# Motor_Control_Thermal_Vias.net
KiCad netlist of a schematic drawn in EAGLE
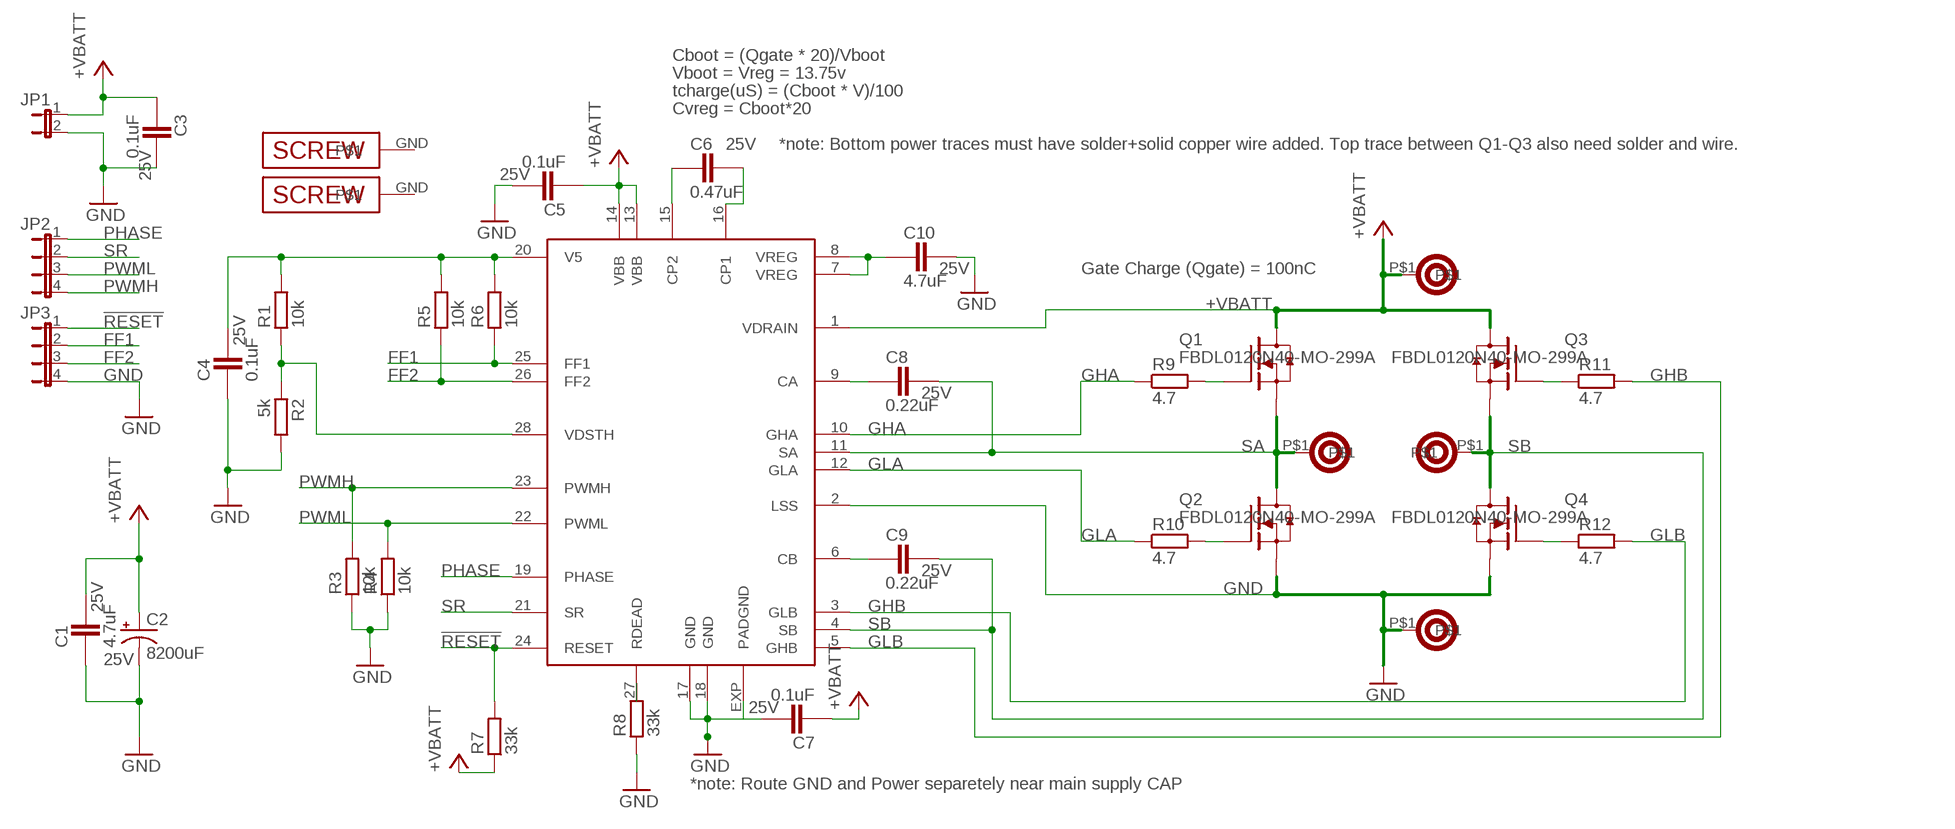
[diagram p0: schematic, sheet 1]

(export (version "E")
  (design (tool "Eeschema 10.0.6"))
  (components
    (comp (ref "C1")
      (value "4.7uF")
      (footprint "eagle-import:CAPC1608X92N")
      (fields (field (name "VOLTAGE") "25V"))
      (libsource (lib "eagle-import") (part "CAPACITOR_0603"))
    )
    (comp (ref "C2")
      (value "8200uF")
      (footprint "eagle-import:CAP-10-22")
      (fields
        (field (name "MANUFACTURER") "Panasonic")
        (field (name "MANUFACTURER_PART_NUMBER") "ECO-S1EA822BA")
        (field (name "VOLTAGE") "25V")
      )
      (libsource (lib "eagle-import") (part "CPOL-US-PTH-10-22"))
    )
    (comp (ref "C3")
      (value "0.1uF")
      (footprint "eagle-import:CAPC1608X92N")
      (fields (field (name "VOLTAGE") "25V"))
      (libsource (lib "eagle-import") (part "CAPACITOR_0603"))
    )
    (comp (ref "C4")
      (value "0.1uF")
      (footprint "eagle-import:CAPC_0603_LONG")
      (fields (field (name "VOLTAGE") "25V"))
      (libsource (lib "eagle-import") (part "CAPACITOR_0603L"))
    )
    (comp (ref "C5")
      (value "0.1uF")
      (footprint "eagle-import:CAPC1608X92N")
      (fields (field (name "VOLTAGE") "25V"))
      (libsource (lib "eagle-import") (part "CAPACITOR_0603"))
    )
    (comp (ref "C6")
      (value "0.47uF")
      (footprint "eagle-import:CAPC1608X92N")
      (fields (field (name "VOLTAGE") "25V"))
      (libsource (lib "eagle-import") (part "CAPACITOR_0603"))
    )
    (comp (ref "C7")
      (value "0.1uF")
      (footprint "eagle-import:CAPC1608X92N")
      (fields (field (name "VOLTAGE") "25V"))
      (libsource (lib "eagle-import") (part "CAPACITOR_0603"))
    )
    (comp (ref "C8")
      (value "0.22uF")
      (footprint "eagle-import:CAPC_0603_LONG")
      (fields (field (name "VOLTAGE") "25V"))
      (libsource (lib "eagle-import") (part "CAPACITOR_0603L"))
    )
    (comp (ref "C9")
      (value "0.22uF")
      (footprint "eagle-import:CAPC_0603_LONG")
      (fields (field (name "VOLTAGE") "25V"))
      (libsource (lib "eagle-import") (part "CAPACITOR_0603L"))
    )
    (comp (ref "C10")
      (value "4.7uF")
      (footprint "eagle-import:CAPC1608X92N")
      (fields (field (name "VOLTAGE") "25V"))
      (libsource (lib "eagle-import") (part "CAPACITOR_0603"))
    )
    (comp (ref "J1")
      (value "63971-1-QC_TAB-RA")
      (footprint "eagle-import:QUICK_CONN_TAB-RA")
      (fields
        (field (name "MANUFACTURER") "TE Connectivity")
        (field (name "MANUFACTURER_PART_NUMBER") "63971-1")
      )
      (libsource (lib "eagle-import") (part "63971-1-QC_TAB-RA"))
    )
    (comp (ref "J2")
      (value "63971-1-QC_TAB-RA")
      (footprint "eagle-import:QUICK_CONN_TAB-RA")
      (fields
        (field (name "MANUFACTURER") "TE Connectivity")
        (field (name "MANUFACTURER_PART_NUMBER") "63971-1")
      )
      (libsource (lib "eagle-import") (part "63971-1-QC_TAB-RA"))
    )
    (comp (ref "J3")
      (value "63971-1-QC_TAB-RA")
      (footprint "eagle-import:QUICK_CONN_TAB-RA")
      (fields
        (field (name "MANUFACTURER") "TE Connectivity")
        (field (name "MANUFACTURER_PART_NUMBER") "63971-1")
      )
      (libsource (lib "eagle-import") (part "63971-1-QC_TAB-RA"))
    )
    (comp (ref "J4")
      (value "63971-1-QC_TAB-RA")
      (footprint "eagle-import:QUICK_CONN_TAB-RA")
      (fields
        (field (name "MANUFACTURER") "TE Connectivity")
        (field (name "MANUFACTURER_PART_NUMBER") "63971-1")
      )
      (libsource (lib "eagle-import") (part "63971-1-QC_TAB-RA"))
    )
    (comp (ref "JP1")
      (value "JP1E")
      (footprint "eagle-import:JP1")
      (libsource (lib "eagle-import") (part "JP1E"))
    )
    (comp (ref "JP2")
      (value "JP4E")
      (footprint "eagle-import:JP4")
      (libsource (lib "eagle-import") (part "JP4E"))
    )
    (comp (ref "JP3")
      (value "JP4E")
      (footprint "eagle-import:JP4")
      (libsource (lib "eagle-import") (part "JP4E"))
    )
    (comp (ref "Q1")
      (value "FBDL0120N40-MO-299A")
      (footprint "eagle-import:MO-299")
      (fields
        (field (name "MANUFACTURER") "Fairchild")
        (field (name "MANUFACTURER_PART_NUMBER") "FDBL0120N40")
      )
      (libsource (lib "eagle-import") (part "FBDL0120N40-MO-299A"))
    )
    (comp (ref "Q2")
      (value "FBDL0120N40-MO-299A")
      (footprint "eagle-import:MO-299")
      (fields
        (field (name "MANUFACTURER") "Fairchild")
        (field (name "MANUFACTURER_PART_NUMBER") "FDBL0120N40")
      )
      (libsource (lib "eagle-import") (part "FBDL0120N40-MO-299A"))
    )
    (comp (ref "Q3")
      (value "FBDL0120N40-MO-299A")
      (footprint "eagle-import:MO-299")
      (fields
        (field (name "MANUFACTURER") "Fairchild")
        (field (name "MANUFACTURER_PART_NUMBER") "FDBL0120N40")
      )
      (libsource (lib "eagle-import") (part "FBDL0120N40-MO-299A"))
    )
    (comp (ref "Q4")
      (value "FBDL0120N40-MO-299A")
      (footprint "eagle-import:MO-299")
      (fields
        (field (name "MANUFACTURER") "Fairchild")
        (field (name "MANUFACTURER_PART_NUMBER") "FDBL0120N40")
      )
      (libsource (lib "eagle-import") (part "FBDL0120N40-MO-299A"))
    )
    (comp (ref "R1")
      (value "10k")
      (footprint "eagle-import:RESC1608X55N")
      (libsource (lib "eagle-import") (part "RESISTOR_0603"))
    )
    (comp (ref "R2")
      (value "5k")
      (footprint "eagle-import:RESC1608X55N")
      (libsource (lib "eagle-import") (part "RESISTOR_0603"))
    )
    (comp (ref "R3")
      (value "10k")
      (footprint "eagle-import:RESC1608X55N")
      (libsource (lib "eagle-import") (part "RESISTOR_0603"))
    )
    (comp (ref "R4")
      (value "10k")
      (footprint "eagle-import:RESC1608X55N")
      (libsource (lib "eagle-import") (part "RESISTOR_0603"))
    )
    (comp (ref "R5")
      (value "10k")
      (footprint "eagle-import:RESC1608X55N")
      (libsource (lib "eagle-import") (part "RESISTOR_0603"))
    )
    (comp (ref "R6")
      (value "10k")
      (footprint "eagle-import:RESC1608X55N")
      (libsource (lib "eagle-import") (part "RESISTOR_0603"))
    )
    (comp (ref "R7")
      (value "33k")
      (footprint "eagle-import:RESC1608X55N")
      (libsource (lib "eagle-import") (part "RESISTOR_0603"))
    )
    (comp (ref "R8")
      (value "33k")
      (footprint "eagle-import:RESC1608X55N")
      (libsource (lib "eagle-import") (part "RESISTOR_0603"))
    )
    (comp (ref "R9")
      (value "4.7")
      (footprint "eagle-import:RESC1608X55N")
      (libsource (lib "eagle-import") (part "RESISTOR_0603"))
    )
    (comp (ref "R10")
      (value "4.7")
      (footprint "eagle-import:RESC1608X55N")
      (libsource (lib "eagle-import") (part "RESISTOR_0603"))
    )
    (comp (ref "R11")
      (value "4.7")
      (footprint "eagle-import:RESC1608X55N")
      (libsource (lib "eagle-import") (part "RESISTOR_0603"))
    )
    (comp (ref "R12")
      (value "4.7")
      (footprint "eagle-import:RESC1608X55N")
      (libsource (lib "eagle-import") (part "RESISTOR_0603"))
    )
    (comp (ref "SCREW1")
      (value "SCREW-4MM")
      (footprint "eagle-import:PLATEDSCREW-4MM")
      (libsource (lib "eagle-import") (part "SCREW-4MM"))
    )
    (comp (ref "SCREW2")
      (value "SCREW-4MM")
      (footprint "eagle-import:PLATEDSCREW-4MM")
      (libsource (lib "eagle-import") (part "SCREW-4MM"))
    )
    (comp (ref "U1")
      (value "A3941-TSSOP28-LP")
      (footprint "eagle-import:TSSOP28-LP")
      (fields
        (field (name "MANUFACTURER") "Allegro MicroSystems LLC")
        (field (name "MANUFACTURER_PART_NUMBER") "A3941")
      )
      (libsource (lib "eagle-import") (part "A3941-TSSOP28-LP"))
    )
  )
  (nets
    (net (code "1") (name "+VBATT") (class "Default")
      (node (ref "C1") (pin "2") (pinfunction "2_2") (pintype "passive"))
      (node (ref "C2") (pin "+") (pinfunction "+_+") (pintype "passive"))
      (node (ref "C3") (pin "1") (pinfunction "1_1") (pintype "passive"))
      (node (ref "C5") (pin "1") (pinfunction "1_1") (pintype "passive"))
      (node (ref "C7") (pin "1") (pinfunction "1_1") (pintype "passive"))
      (node (ref "J2") (pin "P$1") (pinfunction "P$1_P$1") (pintype "bidirectional"))
      (node (ref "JP1") (pin "1") (pinfunction "1_1") (pintype "passive"))
      (node (ref "Q1") (pin "P$9") (pinfunction "D_P$9") (pintype "passive"))
      (node (ref "Q3") (pin "P$9") (pinfunction "D_P$9") (pintype "passive"))
      (node (ref "R7") (pin "1") (pinfunction "1_1") (pintype "passive"))
      (node (ref "U1") (pin "1") (pinfunction "VDRAIN_1") (pintype "bidirectional"))
      (node (ref "U1") (pin "13") (pinfunction "VBB_13") (pintype "bidirectional"))
      (node (ref "U1") (pin "14") (pinfunction "VBB_14") (pintype "bidirectional"))
    )
    (net (code "2") (name "/FF1") (class "Default")
      (node (ref "JP3") (pin "2") (pinfunction "2_2") (pintype "passive"))
      (node (ref "R6") (pin "1") (pinfunction "1_1") (pintype "passive"))
      (node (ref "U1") (pin "25") (pinfunction "FF1_25") (pintype "output"))
    )
    (net (code "3") (name "/FF2") (class "Default")
      (node (ref "JP3") (pin "3") (pinfunction "3_3") (pintype "passive"))
      (node (ref "R5") (pin "1") (pinfunction "1_1") (pintype "passive"))
      (node (ref "U1") (pin "26") (pinfunction "FF2_26") (pintype "output"))
    )
    (net (code "4") (name "/GHA") (class "Default")
      (node (ref "R9") (pin "1") (pinfunction "1_1") (pintype "passive"))
      (node (ref "U1") (pin "10") (pinfunction "GHA_10") (pintype "output"))
    )
    (net (code "5") (name "/GHB") (class "Default")
      (node (ref "R11") (pin "2") (pinfunction "2_2") (pintype "passive"))
      (node (ref "U1") (pin "5") (pinfunction "GHB_5") (pintype "output"))
    )
    (net (code "6") (name "/GLA") (class "Default")
      (node (ref "R10") (pin "1") (pinfunction "1_1") (pintype "passive"))
      (node (ref "U1") (pin "12") (pinfunction "GLA_12") (pintype "output"))
    )
    (net (code "7") (name "/GLB") (class "Default")
      (node (ref "R12") (pin "2") (pinfunction "2_2") (pintype "passive"))
      (node (ref "U1") (pin "3") (pinfunction "GLB_3") (pintype "output"))
    )
    (net (code "8") (name "/PHASE") (class "Default")
      (node (ref "JP2") (pin "1") (pinfunction "1_1") (pintype "passive"))
      (node (ref "U1") (pin "19") (pinfunction "PHASE_19") (pintype "input"))
    )
    (net (code "9") (name "/PWMH") (class "Default")
      (node (ref "JP2") (pin "4") (pinfunction "4_4") (pintype "passive"))
      (node (ref "R3") (pin "2") (pinfunction "2_2") (pintype "passive"))
      (node (ref "U1") (pin "23") (pinfunction "PWMH_23") (pintype "input"))
    )
    (net (code "10") (name "/PWML") (class "Default")
      (node (ref "JP2") (pin "3") (pinfunction "3_3") (pintype "passive"))
      (node (ref "R4") (pin "2") (pinfunction "2_2") (pintype "passive"))
      (node (ref "U1") (pin "22") (pinfunction "PWML_22") (pintype "input"))
    )
    (net (code "11") (name "/SA") (class "Default")
      (node (ref "C8") (pin "2") (pinfunction "2_2") (pintype "passive"))
      (node (ref "J1") (pin "P$1") (pinfunction "P$1_P$1") (pintype "bidirectional"))
      (node (ref "Q1") (pin "P$2") (pinfunction "S_P$2") (pintype "passive"))
      (node (ref "Q1") (pin "P$3") (pinfunction "S_P$3") (pintype "passive"))
      (node (ref "Q1") (pin "P$4") (pinfunction "S_P$4") (pintype "passive"))
      (node (ref "Q1") (pin "P$5") (pinfunction "S_P$5") (pintype "passive"))
      (node (ref "Q1") (pin "P$6") (pinfunction "S_P$6") (pintype "passive"))
      (node (ref "Q1") (pin "P$7") (pinfunction "S_P$7") (pintype "passive"))
      (node (ref "Q1") (pin "P$8") (pinfunction "S_P$8") (pintype "passive"))
      (node (ref "Q2") (pin "P$9") (pinfunction "D_P$9") (pintype "passive"))
      (node (ref "U1") (pin "11") (pinfunction "SA_11") (pintype "bidirectional"))
    )
    (net (code "12") (name "/SB") (class "Default")
      (node (ref "C9") (pin "2") (pinfunction "2_2") (pintype "passive"))
      (node (ref "J3") (pin "P$1") (pinfunction "P$1_P$1") (pintype "bidirectional"))
      (node (ref "Q3") (pin "P$2") (pinfunction "S_P$2") (pintype "passive"))
      (node (ref "Q3") (pin "P$3") (pinfunction "S_P$3") (pintype "passive"))
      (node (ref "Q3") (pin "P$4") (pinfunction "S_P$4") (pintype "passive"))
      (node (ref "Q3") (pin "P$5") (pinfunction "S_P$5") (pintype "passive"))
      (node (ref "Q3") (pin "P$6") (pinfunction "S_P$6") (pintype "passive"))
      (node (ref "Q3") (pin "P$7") (pinfunction "S_P$7") (pintype "passive"))
      (node (ref "Q3") (pin "P$8") (pinfunction "S_P$8") (pintype "passive"))
      (node (ref "Q4") (pin "P$9") (pinfunction "D_P$9") (pintype "passive"))
      (node (ref "U1") (pin "4") (pinfunction "SB_4") (pintype "bidirectional"))
    )
    (net (code "13") (name "/SR") (class "Default")
      (node (ref "JP2") (pin "2") (pinfunction "2_2") (pintype "passive"))
      (node (ref "U1") (pin "21") (pinfunction "SR_21") (pintype "input"))
    )
    (net (code "14") (name "/~{RESET}") (class "Default")
      (node (ref "JP3") (pin "1") (pinfunction "1_1") (pintype "passive"))
      (node (ref "R7") (pin "2") (pinfunction "2_2") (pintype "passive"))
      (node (ref "U1") (pin "24") (pinfunction "RESET_24") (pintype "input"))
    )
    (net (code "15") (name "GND") (class "Default")
      (node (ref "C1") (pin "1") (pinfunction "1_1") (pintype "passive"))
      (node (ref "C10") (pin "2") (pinfunction "2_2") (pintype "passive"))
      (node (ref "C2") (pin "-") (pinfunction "-_-") (pintype "passive"))
      (node (ref "C3") (pin "2") (pinfunction "2_2") (pintype "passive"))
      (node (ref "C4") (pin "1") (pinfunction "1_1") (pintype "passive"))
      (node (ref "C5") (pin "2") (pinfunction "2_2") (pintype "passive"))
      (node (ref "C7") (pin "2") (pinfunction "2_2") (pintype "passive"))
      (node (ref "J4") (pin "P$1") (pinfunction "P$1_P$1") (pintype "bidirectional"))
      (node (ref "JP1") (pin "2") (pinfunction "2_2") (pintype "passive"))
      (node (ref "JP3") (pin "4") (pinfunction "4_4") (pintype "passive"))
      (node (ref "Q2") (pin "P$2") (pinfunction "S_P$2") (pintype "passive"))
      (node (ref "Q2") (pin "P$3") (pinfunction "S_P$3") (pintype "passive"))
      (node (ref "Q2") (pin "P$4") (pinfunction "S_P$4") (pintype "passive"))
      (node (ref "Q2") (pin "P$5") (pinfunction "S_P$5") (pintype "passive"))
      (node (ref "Q2") (pin "P$6") (pinfunction "S_P$6") (pintype "passive"))
      (node (ref "Q2") (pin "P$7") (pinfunction "S_P$7") (pintype "passive"))
      (node (ref "Q2") (pin "P$8") (pinfunction "S_P$8") (pintype "passive"))
      (node (ref "Q4") (pin "P$2") (pinfunction "S_P$2") (pintype "passive"))
      (node (ref "Q4") (pin "P$3") (pinfunction "S_P$3") (pintype "passive"))
      (node (ref "Q4") (pin "P$4") (pinfunction "S_P$4") (pintype "passive"))
      (node (ref "Q4") (pin "P$5") (pinfunction "S_P$5") (pintype "passive"))
      (node (ref "Q4") (pin "P$6") (pinfunction "S_P$6") (pintype "passive"))
      (node (ref "Q4") (pin "P$7") (pinfunction "S_P$7") (pintype "passive"))
      (node (ref "Q4") (pin "P$8") (pinfunction "S_P$8") (pintype "passive"))
      (node (ref "R2") (pin "2") (pinfunction "2_2") (pintype "passive"))
      (node (ref "R3") (pin "1") (pinfunction "1_1") (pintype "passive"))
      (node (ref "R4") (pin "1") (pinfunction "1_1") (pintype "passive"))
      (node (ref "R8") (pin "1") (pinfunction "1_1") (pintype "passive"))
      (node (ref "U1") (pin "17") (pinfunction "GND_17") (pintype "bidirectional"))
      (node (ref "U1") (pin "18") (pinfunction "GND_18") (pintype "bidirectional"))
      (node (ref "U1") (pin "2") (pinfunction "LSS_2") (pintype "bidirectional"))
      (node (ref "U1") (pin "EXP") (pinfunction "PADGND_EXP") (pintype "bidirectional"))
    )
    (net (code "16") (name "Net-(C10-Pad1)") (class "Default")
      (node (ref "C10") (pin "1") (pinfunction "1_1") (pintype "passive"))
      (node (ref "U1") (pin "7") (pinfunction "VREG_7") (pintype "bidirectional"))
      (node (ref "U1") (pin "8") (pinfunction "VREG_8") (pintype "bidirectional"))
    )
    (net (code "17") (name "Net-(Q1-G)") (class "Default")
      (node (ref "Q1") (pin "P$1") (pinfunction "G_P$1") (pintype "passive"))
      (node (ref "R9") (pin "2") (pinfunction "2_2") (pintype "passive"))
    )
    (net (code "18") (name "Net-(Q2-G)") (class "Default")
      (node (ref "Q2") (pin "P$1") (pinfunction "G_P$1") (pintype "passive"))
      (node (ref "R10") (pin "2") (pinfunction "2_2") (pintype "passive"))
    )
    (net (code "19") (name "Net-(Q3-G)") (class "Default")
      (node (ref "Q3") (pin "P$1") (pinfunction "G_P$1") (pintype "passive"))
      (node (ref "R11") (pin "1") (pinfunction "1_1") (pintype "passive"))
    )
    (net (code "20") (name "Net-(Q4-G)") (class "Default")
      (node (ref "Q4") (pin "P$1") (pinfunction "G_P$1") (pintype "passive"))
      (node (ref "R12") (pin "1") (pinfunction "1_1") (pintype "passive"))
    )
    (net (code "21") (name "Net-(U1-CA)") (class "Default")
      (node (ref "C8") (pin "1") (pinfunction "1_1") (pintype "passive"))
      (node (ref "U1") (pin "9") (pinfunction "CA_9") (pintype "bidirectional"))
    )
    (net (code "22") (name "Net-(U1-CB)") (class "Default")
      (node (ref "C9") (pin "1") (pinfunction "1_1") (pintype "passive"))
      (node (ref "U1") (pin "6") (pinfunction "CB_6") (pintype "bidirectional"))
    )
    (net (code "23") (name "Net-(U1-CP1)") (class "Default")
      (node (ref "C6") (pin "2") (pinfunction "2_2") (pintype "passive"))
      (node (ref "U1") (pin "16") (pinfunction "CP1_16") (pintype "bidirectional"))
    )
    (net (code "24") (name "Net-(U1-CP2)") (class "Default")
      (node (ref "C6") (pin "1") (pinfunction "1_1") (pintype "passive"))
      (node (ref "U1") (pin "15") (pinfunction "CP2_15") (pintype "bidirectional"))
    )
    (net (code "25") (name "Net-(U1-RDEAD)") (class "Default")
      (node (ref "R8") (pin "2") (pinfunction "2_2") (pintype "passive"))
      (node (ref "U1") (pin "27") (pinfunction "RDEAD_27") (pintype "bidirectional"))
    )
    (net (code "26") (name "Net-(U1-V5)") (class "Default")
      (node (ref "C4") (pin "2") (pinfunction "2_2") (pintype "passive"))
      (node (ref "R1") (pin "2") (pinfunction "2_2") (pintype "passive"))
      (node (ref "R5") (pin "2") (pinfunction "2_2") (pintype "passive"))
      (node (ref "R6") (pin "2") (pinfunction "2_2") (pintype "passive"))
      (node (ref "U1") (pin "20") (pinfunction "V5_20") (pintype "bidirectional"))
    )
    (net (code "27") (name "Net-(U1-VDSTH)") (class "Default")
      (node (ref "R1") (pin "1") (pinfunction "1_1") (pintype "passive"))
      (node (ref "R2") (pin "1") (pinfunction "1_1") (pintype "passive"))
      (node (ref "U1") (pin "28") (pinfunction "VDSTH_28") (pintype "input"))
    )
    (net (code "28") (name "unconnected-(SCREW1-P$1-PadGND)") (class "Default")
      (node (ref "SCREW1") (pin "GND") (pinfunction "P$1_GND") (pintype "bidirectional"))
    )
    (net (code "29") (name "unconnected-(SCREW2-P$1-PadGND)") (class "Default")
      (node (ref "SCREW2") (pin "GND") (pinfunction "P$1_GND") (pintype "bidirectional"))
    )
  )
)
